# MaTouch_DevKit_Relay_V1_2.net
KiCad netlist of a schematic drawn in EAGLE
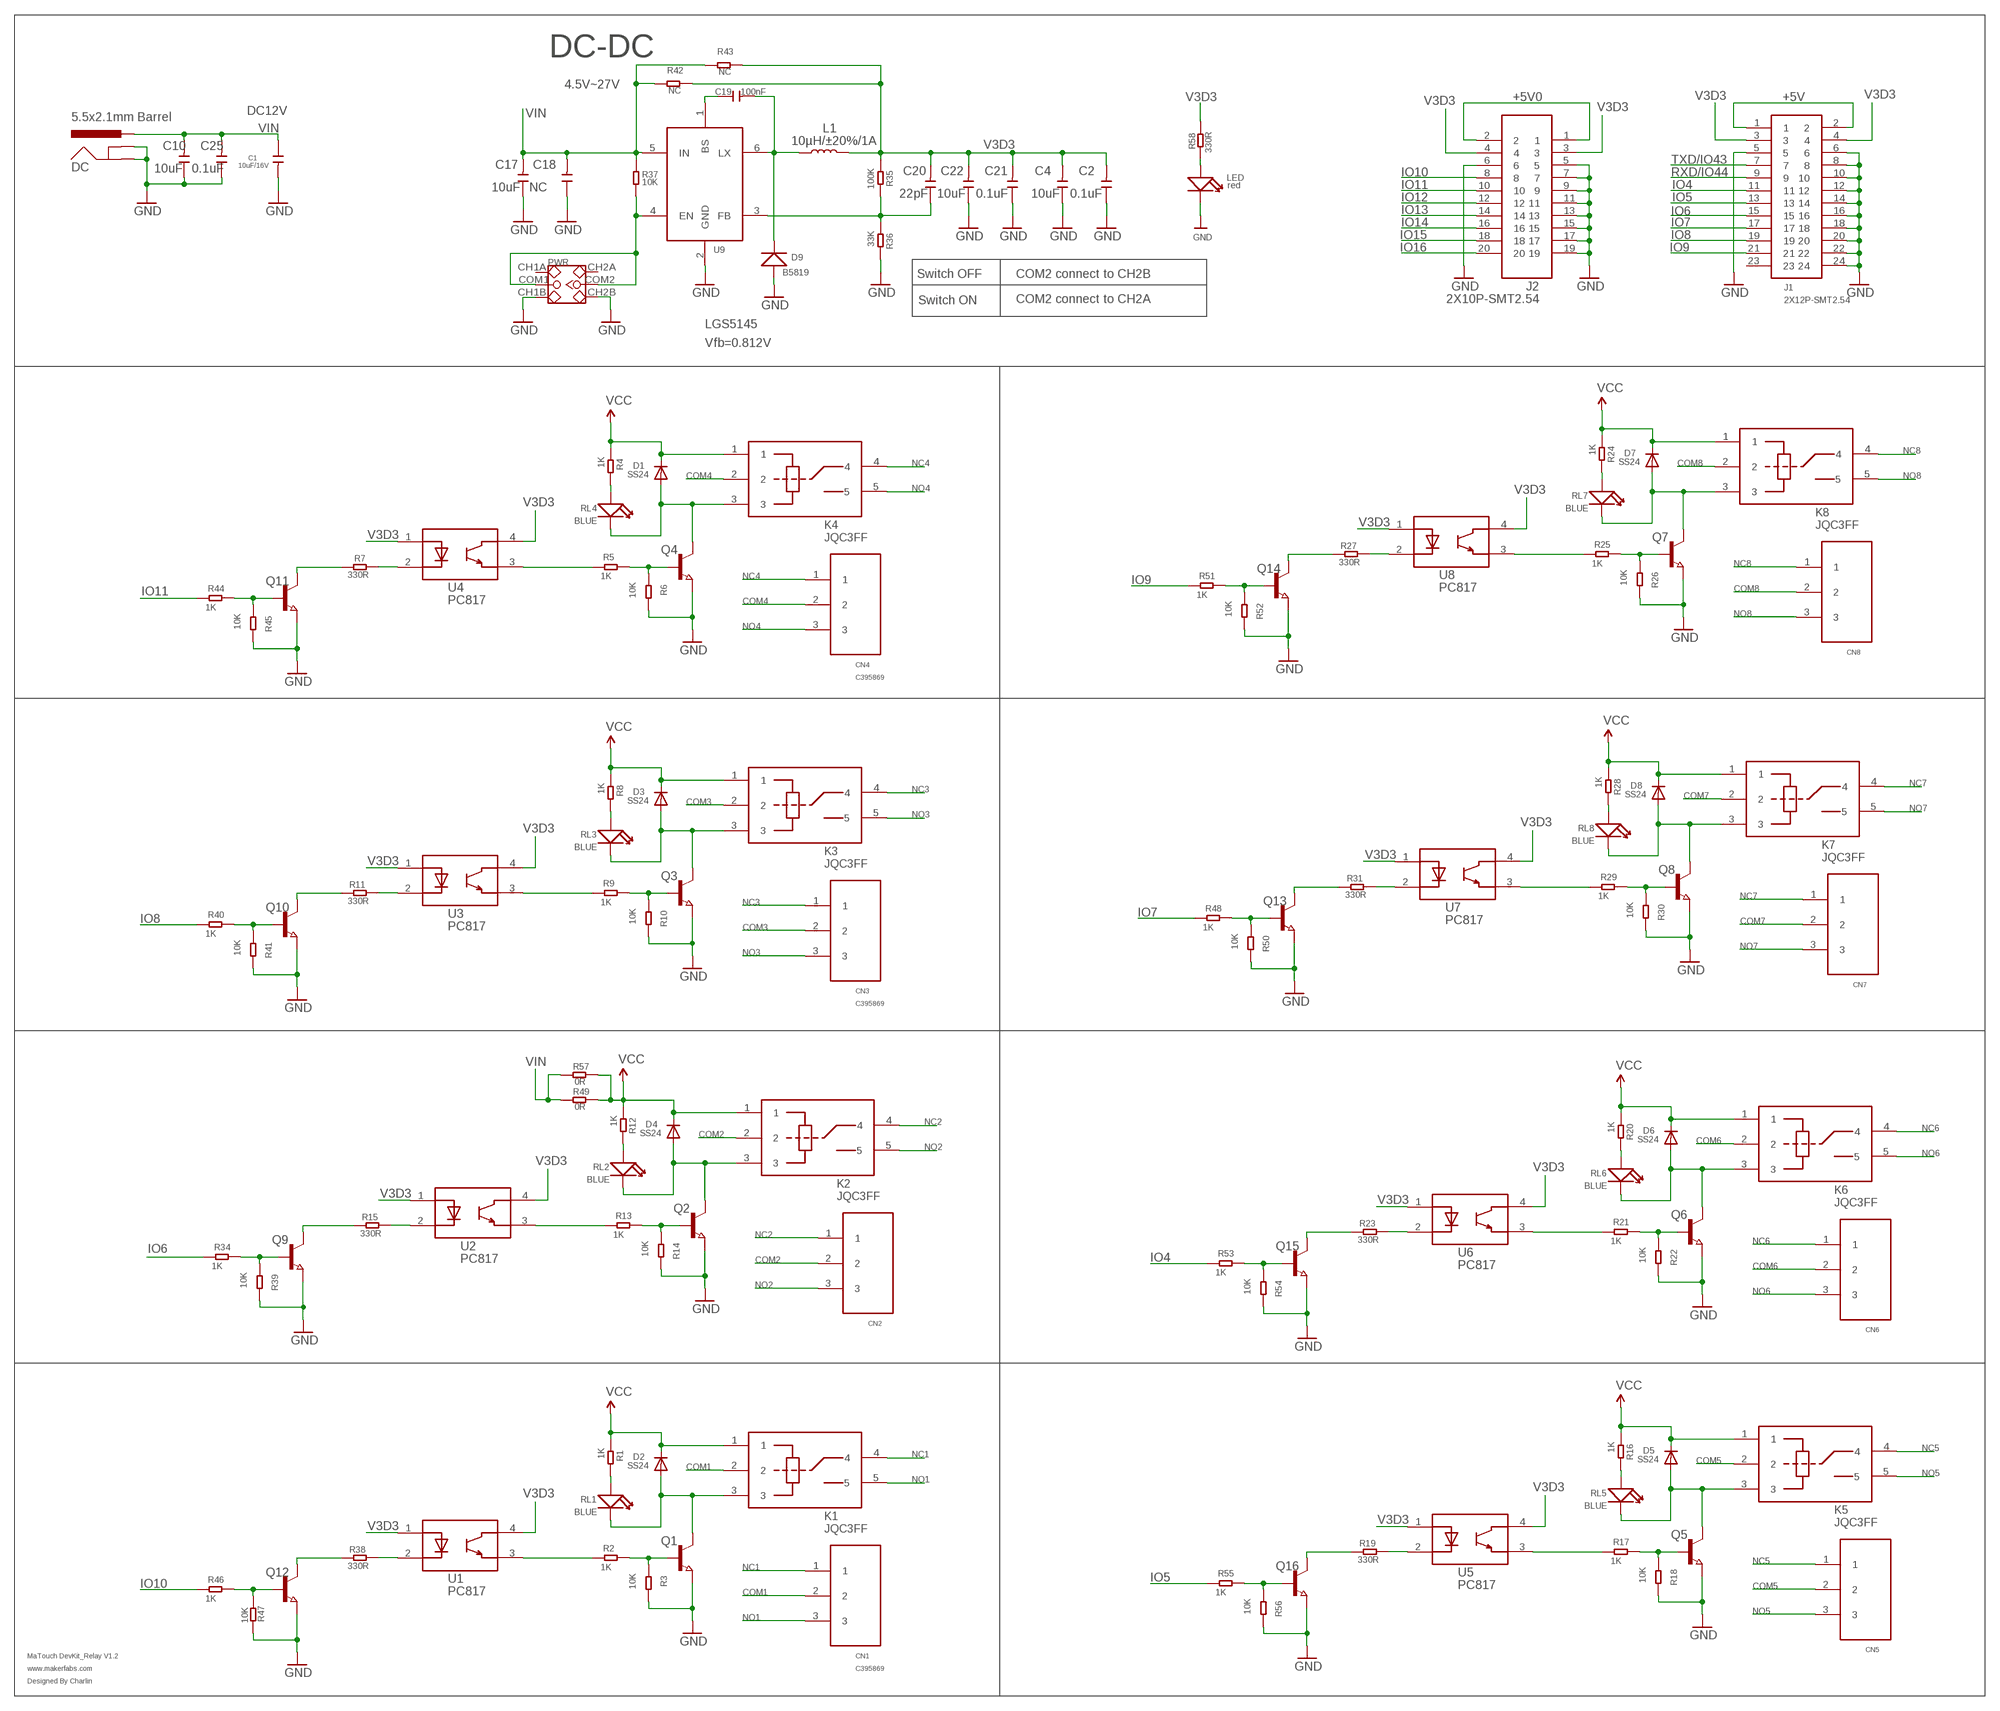
[diagram p0: schematic, sheet 1]

(export (version "E")
  (design (tool "Eeschema 10.0.6"))
  (components
    (comp (ref "C1")
      (value "10uF/16V")
      (footprint "eagle-import:0603")
      (libsource (lib "eagle-import") (part "C-0603"))
    )
    (comp (ref "C2")
      (value "0.1uF")
      (footprint "eagle-import:0603")
      (libsource (lib "eagle-import") (part "C-0603"))
    )
    (comp (ref "C4")
      (value "10uF")
      (footprint "eagle-import:0603")
      (libsource (lib "eagle-import") (part "C-0603"))
    )
    (comp (ref "C10")
      (value "10uF")
      (footprint "eagle-import:0603")
      (libsource (lib "eagle-import") (part "C-0603"))
    )
    (comp (ref "C17")
      (value "10uF")
      (footprint "eagle-import:0603")
      (libsource (lib "eagle-import") (part "C-0603"))
    )
    (comp (ref "C18")
      (value "NC")
      (footprint "eagle-import:0603")
      (libsource (lib "eagle-import") (part "C-0603"))
    )
    (comp (ref "C19")
      (value "100nF")
      (footprint "eagle-import:0603")
      (libsource (lib "eagle-import") (part "C-0603"))
    )
    (comp (ref "C20")
      (value "22pF")
      (footprint "eagle-import:0603")
      (libsource (lib "eagle-import") (part "C-0603"))
    )
    (comp (ref "C21")
      (value "0.1uF")
      (footprint "eagle-import:0603")
      (libsource (lib "eagle-import") (part "C-0603"))
    )
    (comp (ref "C22")
      (value "10uF")
      (footprint "eagle-import:0603")
      (libsource (lib "eagle-import") (part "C-0603"))
    )
    (comp (ref "C25")
      (value "0.1uF")
      (footprint "eagle-import:0603")
      (libsource (lib "eagle-import") (part "C-0603"))
    )
    (comp (ref "CN1")
      (value "C395869")
      (footprint "eagle-import:PIN_3P")
      (libsource (lib "eagle-import") (part "C395869"))
    )
    (comp (ref "CN2")
      (value "C395869")
      (footprint "eagle-import:PIN_3P")
      (libsource (lib "eagle-import") (part "C395869"))
    )
    (comp (ref "CN3")
      (value "C395869")
      (footprint "eagle-import:PIN_3P")
      (libsource (lib "eagle-import") (part "C395869"))
    )
    (comp (ref "CN4")
      (value "C395869")
      (footprint "eagle-import:PIN_3P")
      (libsource (lib "eagle-import") (part "C395869"))
    )
    (comp (ref "CN5")
      (value "C395869")
      (footprint "eagle-import:PIN_3P")
      (libsource (lib "eagle-import") (part "C395869"))
    )
    (comp (ref "CN6")
      (value "C395869")
      (footprint "eagle-import:PIN_3P")
      (libsource (lib "eagle-import") (part "C395869"))
    )
    (comp (ref "CN7")
      (value "C395869")
      (footprint "eagle-import:PIN_3P")
      (libsource (lib "eagle-import") (part "C395869"))
    )
    (comp (ref "CN8")
      (value "C395869")
      (footprint "eagle-import:PIN_3P")
      (libsource (lib "eagle-import") (part "C395869"))
    )
    (comp (ref "D1")
      (value "SS24")
      (footprint "eagle-import:SMADIODE")
      (libsource (lib "eagle-import") (part "DIODESMA"))
    )
    (comp (ref "D2")
      (value "SS24")
      (footprint "eagle-import:SMADIODE")
      (libsource (lib "eagle-import") (part "DIODESMA"))
    )
    (comp (ref "D3")
      (value "SS24")
      (footprint "eagle-import:SMADIODE")
      (libsource (lib "eagle-import") (part "DIODESMA"))
    )
    (comp (ref "D4")
      (value "SS24")
      (footprint "eagle-import:SMADIODE")
      (libsource (lib "eagle-import") (part "DIODESMA"))
    )
    (comp (ref "D5")
      (value "SS24")
      (footprint "eagle-import:SMADIODE")
      (libsource (lib "eagle-import") (part "DIODESMA"))
    )
    (comp (ref "D6")
      (value "SS24")
      (footprint "eagle-import:SMADIODE")
      (libsource (lib "eagle-import") (part "DIODESMA"))
    )
    (comp (ref "D7")
      (value "SS24")
      (footprint "eagle-import:SMADIODE")
      (libsource (lib "eagle-import") (part "DIODESMA"))
    )
    (comp (ref "D8")
      (value "SS24")
      (footprint "eagle-import:SMADIODE")
      (libsource (lib "eagle-import") (part "DIODESMA"))
    )
    (comp (ref "D9")
      (value "B5819")
      (footprint "eagle-import:SOD123")
      (libsource (lib "eagle-import") (part "D'1206'"))
    )
    (comp (ref "DC")
      (value "5.5x2.1mm Barrel")
      (footprint "eagle-import:POWER_JACK_SMD")
      (libsource (lib "eagle-import") (part "POWER_JACKSMD"))
    )
    (comp (ref "J1")
      (value "2X12P-SMT2.54")
      (footprint "eagle-import:2X12P-SMT2.54")
      (libsource (lib "eagle-import") (part "2X12P-SMT2.54"))
    )
    (comp (ref "J2")
      (value "2X10P-SMT2.54")
      (footprint "eagle-import:2X10P-SMT2.54")
      (libsource (lib "eagle-import") (part "2X10P-SMT2.54"))
    )
    (comp (ref "K1")
      (value "JQC3FF")
      (footprint "eagle-import:DIP5_JQC3FF")
      (libsource (lib "eagle-import") (part "JQC3FF"))
    )
    (comp (ref "K2")
      (value "JQC3FF")
      (footprint "eagle-import:DIP5_JQC3FF")
      (libsource (lib "eagle-import") (part "JQC3FF"))
    )
    (comp (ref "K3")
      (value "JQC3FF")
      (footprint "eagle-import:DIP5_JQC3FF")
      (libsource (lib "eagle-import") (part "JQC3FF"))
    )
    (comp (ref "K4")
      (value "JQC3FF")
      (footprint "eagle-import:DIP5_JQC3FF")
      (libsource (lib "eagle-import") (part "JQC3FF"))
    )
    (comp (ref "K5")
      (value "JQC3FF")
      (footprint "eagle-import:DIP5_JQC3FF")
      (libsource (lib "eagle-import") (part "JQC3FF"))
    )
    (comp (ref "K6")
      (value "JQC3FF")
      (footprint "eagle-import:DIP5_JQC3FF")
      (libsource (lib "eagle-import") (part "JQC3FF"))
    )
    (comp (ref "K7")
      (value "JQC3FF")
      (footprint "eagle-import:DIP5_JQC3FF")
      (libsource (lib "eagle-import") (part "JQC3FF"))
    )
    (comp (ref "K8")
      (value "JQC3FF")
      (footprint "eagle-import:DIP5_JQC3FF")
      (libsource (lib "eagle-import") (part "JQC3FF"))
    )
    (comp (ref "L1")
      (value "10µH/±20%/1A")
      (footprint "eagle-import:SRN6045")
      (libsource (lib "eagle-import") (part "INDUCTOR-SRN6045-33UH"))
    )
    (comp (ref "LED")
      (value "red")
      (footprint "eagle-import:DISCRETE_LED-0603")
      (libsource (lib "eagle-import") (part "DISCRETE_LED0603"))
    )
    (comp (ref "PWR")
      (value "SWITCH-2CH-6P")
      (footprint "eagle-import:6P-2CH-2.54-7.6X3.0")
      (libsource (lib "eagle-import") (part "SWITCH-2CH-6P"))
    )
    (comp (ref "Q1")
      (value "NPN-TRANSISTOR_SOT23")
      (footprint "eagle-import:SOT23")
      (libsource (lib "eagle-import") (part "NPN-TRANSISTOR_SOT23"))
    )
    (comp (ref "Q2")
      (value "NPN-TRANSISTOR_SOT23")
      (footprint "eagle-import:SOT23")
      (libsource (lib "eagle-import") (part "NPN-TRANSISTOR_SOT23"))
    )
    (comp (ref "Q3")
      (value "NPN-TRANSISTOR_SOT23")
      (footprint "eagle-import:SOT23")
      (libsource (lib "eagle-import") (part "NPN-TRANSISTOR_SOT23"))
    )
    (comp (ref "Q4")
      (value "NPN-TRANSISTOR_SOT23")
      (footprint "eagle-import:SOT23")
      (libsource (lib "eagle-import") (part "NPN-TRANSISTOR_SOT23"))
    )
    (comp (ref "Q5")
      (value "NPN-TRANSISTOR_SOT23")
      (footprint "eagle-import:SOT23")
      (libsource (lib "eagle-import") (part "NPN-TRANSISTOR_SOT23"))
    )
    (comp (ref "Q6")
      (value "NPN-TRANSISTOR_SOT23")
      (footprint "eagle-import:SOT23")
      (libsource (lib "eagle-import") (part "NPN-TRANSISTOR_SOT23"))
    )
    (comp (ref "Q7")
      (value "NPN-TRANSISTOR_SOT23")
      (footprint "eagle-import:SOT23")
      (libsource (lib "eagle-import") (part "NPN-TRANSISTOR_SOT23"))
    )
    (comp (ref "Q8")
      (value "NPN-TRANSISTOR_SOT23")
      (footprint "eagle-import:SOT23")
      (libsource (lib "eagle-import") (part "NPN-TRANSISTOR_SOT23"))
    )
    (comp (ref "Q9")
      (value "NPN-TRANSISTOR_SOT23")
      (footprint "eagle-import:SOT23")
      (libsource (lib "eagle-import") (part "NPN-TRANSISTOR_SOT23"))
    )
    (comp (ref "Q10")
      (value "NPN-TRANSISTOR_SOT23")
      (footprint "eagle-import:SOT23")
      (libsource (lib "eagle-import") (part "NPN-TRANSISTOR_SOT23"))
    )
    (comp (ref "Q11")
      (value "NPN-TRANSISTOR_SOT23")
      (footprint "eagle-import:SOT23")
      (libsource (lib "eagle-import") (part "NPN-TRANSISTOR_SOT23"))
    )
    (comp (ref "Q12")
      (value "NPN-TRANSISTOR_SOT23")
      (footprint "eagle-import:SOT23")
      (libsource (lib "eagle-import") (part "NPN-TRANSISTOR_SOT23"))
    )
    (comp (ref "Q13")
      (value "NPN-TRANSISTOR_SOT23")
      (footprint "eagle-import:SOT23")
      (libsource (lib "eagle-import") (part "NPN-TRANSISTOR_SOT23"))
    )
    (comp (ref "Q14")
      (value "NPN-TRANSISTOR_SOT23")
      (footprint "eagle-import:SOT23")
      (libsource (lib "eagle-import") (part "NPN-TRANSISTOR_SOT23"))
    )
    (comp (ref "Q15")
      (value "NPN-TRANSISTOR_SOT23")
      (footprint "eagle-import:SOT23")
      (libsource (lib "eagle-import") (part "NPN-TRANSISTOR_SOT23"))
    )
    (comp (ref "Q16")
      (value "NPN-TRANSISTOR_SOT23")
      (footprint "eagle-import:SOT23")
      (libsource (lib "eagle-import") (part "NPN-TRANSISTOR_SOT23"))
    )
    (comp (ref "R1")
      (value "1K")
      (footprint "eagle-import:R0603")
      (libsource (lib "eagle-import") (part "R-0603"))
    )
    (comp (ref "R2")
      (value "1K")
      (footprint "eagle-import:R0603")
      (libsource (lib "eagle-import") (part "R-0603"))
    )
    (comp (ref "R3")
      (value "10K")
      (footprint "eagle-import:R0603")
      (libsource (lib "eagle-import") (part "R-0603"))
    )
    (comp (ref "R4")
      (value "1K")
      (footprint "eagle-import:R0603")
      (libsource (lib "eagle-import") (part "R-0603"))
    )
    (comp (ref "R5")
      (value "1K")
      (footprint "eagle-import:R0603")
      (libsource (lib "eagle-import") (part "R-0603"))
    )
    (comp (ref "R6")
      (value "10K")
      (footprint "eagle-import:R0603")
      (libsource (lib "eagle-import") (part "R-0603"))
    )
    (comp (ref "R7")
      (value "330R")
      (footprint "eagle-import:R0603")
      (libsource (lib "eagle-import") (part "R-0603"))
    )
    (comp (ref "R8")
      (value "1K")
      (footprint "eagle-import:R0603")
      (libsource (lib "eagle-import") (part "R-0603"))
    )
    (comp (ref "R9")
      (value "1K")
      (footprint "eagle-import:R0603")
      (libsource (lib "eagle-import") (part "R-0603"))
    )
    (comp (ref "R10")
      (value "10K")
      (footprint "eagle-import:R0603")
      (libsource (lib "eagle-import") (part "R-0603"))
    )
    (comp (ref "R11")
      (value "330R")
      (footprint "eagle-import:R0603")
      (libsource (lib "eagle-import") (part "R-0603"))
    )
    (comp (ref "R12")
      (value "1K")
      (footprint "eagle-import:R0603")
      (libsource (lib "eagle-import") (part "R-0603"))
    )
    (comp (ref "R13")
      (value "1K")
      (footprint "eagle-import:R0603")
      (libsource (lib "eagle-import") (part "R-0603"))
    )
    (comp (ref "R14")
      (value "10K")
      (footprint "eagle-import:R0603")
      (libsource (lib "eagle-import") (part "R-0603"))
    )
    (comp (ref "R15")
      (value "330R")
      (footprint "eagle-import:R0603")
      (libsource (lib "eagle-import") (part "R-0603"))
    )
    (comp (ref "R16")
      (value "1K")
      (footprint "eagle-import:R0603")
      (libsource (lib "eagle-import") (part "R-0603"))
    )
    (comp (ref "R17")
      (value "1K")
      (footprint "eagle-import:R0603")
      (libsource (lib "eagle-import") (part "R-0603"))
    )
    (comp (ref "R18")
      (value "10K")
      (footprint "eagle-import:R0603")
      (libsource (lib "eagle-import") (part "R-0603"))
    )
    (comp (ref "R19")
      (value "330R")
      (footprint "eagle-import:R0603")
      (libsource (lib "eagle-import") (part "R-0603"))
    )
    (comp (ref "R20")
      (value "1K")
      (footprint "eagle-import:R0603")
      (libsource (lib "eagle-import") (part "R-0603"))
    )
    (comp (ref "R21")
      (value "1K")
      (footprint "eagle-import:R0603")
      (libsource (lib "eagle-import") (part "R-0603"))
    )
    (comp (ref "R22")
      (value "10K")
      (footprint "eagle-import:R0603")
      (libsource (lib "eagle-import") (part "R-0603"))
    )
    (comp (ref "R23")
      (value "330R")
      (footprint "eagle-import:R0603")
      (libsource (lib "eagle-import") (part "R-0603"))
    )
    (comp (ref "R24")
      (value "1K")
      (footprint "eagle-import:R0603")
      (libsource (lib "eagle-import") (part "R-0603"))
    )
    (comp (ref "R25")
      (value "1K")
      (footprint "eagle-import:R0603")
      (libsource (lib "eagle-import") (part "R-0603"))
    )
    (comp (ref "R26")
      (value "10K")
      (footprint "eagle-import:R0603")
      (libsource (lib "eagle-import") (part "R-0603"))
    )
    (comp (ref "R27")
      (value "330R")
      (footprint "eagle-import:R0603")
      (libsource (lib "eagle-import") (part "R-0603"))
    )
    (comp (ref "R28")
      (value "1K")
      (footprint "eagle-import:R0603")
      (libsource (lib "eagle-import") (part "R-0603"))
    )
    (comp (ref "R29")
      (value "1K")
      (footprint "eagle-import:R0603")
      (libsource (lib "eagle-import") (part "R-0603"))
    )
    (comp (ref "R30")
      (value "10K")
      (footprint "eagle-import:R0603")
      (libsource (lib "eagle-import") (part "R-0603"))
    )
    (comp (ref "R31")
      (value "330R")
      (footprint "eagle-import:R0603")
      (libsource (lib "eagle-import") (part "R-0603"))
    )
    (comp (ref "R34")
      (value "1K")
      (footprint "eagle-import:R0603")
      (libsource (lib "eagle-import") (part "R-0603"))
    )
    (comp (ref "R35")
      (value "100K")
      (footprint "eagle-import:R0603")
      (libsource (lib "eagle-import") (part "R-0603"))
    )
    (comp (ref "R36")
      (value "33K")
      (footprint "eagle-import:R0603")
      (libsource (lib "eagle-import") (part "R-0603"))
    )
    (comp (ref "R37")
      (value "10K")
      (footprint "eagle-import:R0603")
      (libsource (lib "eagle-import") (part "R-0603"))
    )
    (comp (ref "R38")
      (value "330R")
      (footprint "eagle-import:R0603")
      (libsource (lib "eagle-import") (part "R-0603"))
    )
    (comp (ref "R39")
      (value "10K")
      (footprint "eagle-import:R0603")
      (libsource (lib "eagle-import") (part "R-0603"))
    )
    (comp (ref "R40")
      (value "1K")
      (footprint "eagle-import:R0603")
      (libsource (lib "eagle-import") (part "R-0603"))
    )
    (comp (ref "R41")
      (value "10K")
      (footprint "eagle-import:R0603")
      (libsource (lib "eagle-import") (part "R-0603"))
    )
    (comp (ref "R42")
      (value "NC")
      (footprint "eagle-import:R0603")
      (libsource (lib "eagle-import") (part "R-0603"))
    )
    (comp (ref "R43")
      (value "NC")
      (footprint "eagle-import:R0603")
      (libsource (lib "eagle-import") (part "R-0603"))
    )
    (comp (ref "R44")
      (value "1K")
      (footprint "eagle-import:R0603")
      (libsource (lib "eagle-import") (part "R-0603"))
    )
    (comp (ref "R45")
      (value "10K")
      (footprint "eagle-import:R0603")
      (libsource (lib "eagle-import") (part "R-0603"))
    )
    (comp (ref "R46")
      (value "1K")
      (footprint "eagle-import:R0603")
      (libsource (lib "eagle-import") (part "R-0603"))
    )
    (comp (ref "R47")
      (value "10K")
      (footprint "eagle-import:R0603")
      (libsource (lib "eagle-import") (part "R-0603"))
    )
    (comp (ref "R48")
      (value "1K")
      (footprint "eagle-import:R0603")
      (libsource (lib "eagle-import") (part "R-0603"))
    )
    (comp (ref "R49")
      (value "0R")
      (footprint "eagle-import:R0603")
      (libsource (lib "eagle-import") (part "R-0603"))
    )
    (comp (ref "R50")
      (value "10K")
      (footprint "eagle-import:R0603")
      (libsource (lib "eagle-import") (part "R-0603"))
    )
    (comp (ref "R51")
      (value "1K")
      (footprint "eagle-import:R0603")
      (libsource (lib "eagle-import") (part "R-0603"))
    )
    (comp (ref "R52")
      (value "10K")
      (footprint "eagle-import:R0603")
      (libsource (lib "eagle-import") (part "R-0603"))
    )
    (comp (ref "R53")
      (value "1K")
      (footprint "eagle-import:R0603")
      (libsource (lib "eagle-import") (part "R-0603"))
    )
    (comp (ref "R54")
      (value "10K")
      (footprint "eagle-import:R0603")
      (libsource (lib "eagle-import") (part "R-0603"))
    )
    (comp (ref "R55")
      (value "1K")
      (footprint "eagle-import:R0603")
      (libsource (lib "eagle-import") (part "R-0603"))
    )
    (comp (ref "R56")
      (value "10K")
      (footprint "eagle-import:R0603")
      (libsource (lib "eagle-import") (part "R-0603"))
    )
    (comp (ref "R57")
      (value "0R")
      (footprint "eagle-import:R0603")
      (libsource (lib "eagle-import") (part "R-0603"))
    )
    (comp (ref "R58")
      (value "330R")
      (footprint "eagle-import:R0603")
      (libsource (lib "eagle-import") (part "R-0603"))
    )
    (comp (ref "RL1")
      (value "BLUE")
      (footprint "eagle-import:LED-0603")
      (libsource (lib "eagle-import") (part "LED'0603'"))
    )
    (comp (ref "RL2")
      (value "BLUE")
      (footprint "eagle-import:LED-0603")
      (libsource (lib "eagle-import") (part "LED'0603'"))
    )
    (comp (ref "RL3")
      (value "BLUE")
      (footprint "eagle-import:LED-0603")
      (libsource (lib "eagle-import") (part "LED'0603'"))
    )
    (comp (ref "RL4")
      (value "BLUE")
      (footprint "eagle-import:LED-0603")
      (libsource (lib "eagle-import") (part "LED'0603'"))
    )
    (comp (ref "RL5")
      (value "BLUE")
      (footprint "eagle-import:LED-0603")
      (libsource (lib "eagle-import") (part "LED'0603'"))
    )
    (comp (ref "RL6")
      (value "BLUE")
      (footprint "eagle-import:LED-0603")
      (libsource (lib "eagle-import") (part "LED'0603'"))
    )
    (comp (ref "RL7")
      (value "BLUE")
      (footprint "eagle-import:LED-0603")
      (libsource (lib "eagle-import") (part "LED'0603'"))
    )
    (comp (ref "RL8")
      (value "BLUE")
      (footprint "eagle-import:LED-0603")
      (libsource (lib "eagle-import") (part "LED'0603'"))
    )
    (comp (ref "U1")
      (value "PC817")
      (footprint "eagle-import:SMD4-254P-1016L460W")
      (libsource (lib "eagle-import") (part "PC817"))
    )
    (comp (ref "U2")
      (value "PC817")
      (footprint "eagle-import:SMD4-254P-1016L460W")
      (libsource (lib "eagle-import") (part "PC817"))
    )
    (comp (ref "U3")
      (value "PC817")
      (footprint "eagle-import:SMD4-254P-1016L460W")
      (libsource (lib "eagle-import") (part "PC817"))
    )
    (comp (ref "U4")
      (value "PC817")
      (footprint "eagle-import:SMD4-254P-1016L460W")
      (libsource (lib "eagle-import") (part "PC817"))
    )
    (comp (ref "U5")
      (value "PC817")
      (footprint "eagle-import:SMD4-254P-1016L460W")
      (libsource (lib "eagle-import") (part "PC817"))
    )
    (comp (ref "U6")
      (value "PC817")
      (footprint "eagle-import:SMD4-254P-1016L460W")
      (libsource (lib "eagle-import") (part "PC817"))
    )
    (comp (ref "U7")
      (value "PC817")
      (footprint "eagle-import:SMD4-254P-1016L460W")
      (libsource (lib "eagle-import") (part "PC817"))
    )
    (comp (ref "U8")
      (value "PC817")
      (footprint "eagle-import:SMD4-254P-1016L460W")
      (libsource (lib "eagle-import") (part "PC817"))
    )
    (comp (ref "U9")
      (value "SY8201ABC")
      (footprint "eagle-import:SOT-23-6")
      (libsource (lib "eagle-import") (part "SY8201ABC"))
    )
  )
  (nets
    (net (code "1") (name "/+5V") (class "Default")
      (node (ref "J1") (pin "1") (pinfunction "1_1") (pintype "bidirectional"))
      (node (ref "J1") (pin "2") (pinfunction "2_2") (pintype "bidirectional"))
    )
    (net (code "2") (name "/+5V0") (class "Default")
      (node (ref "J2") (pin "1") (pinfunction "1_1") (pintype "bidirectional"))
      (node (ref "J2") (pin "2") (pinfunction "2_2") (pintype "bidirectional"))
    )
    (net (code "3") (name "/COM1") (class "Default")
      (node (ref "CN1") (pin "2") (pinfunction "2_2") (pintype "bidirectional"))
      (node (ref "K1") (pin "2") (pinfunction "2_2") (pintype "bidirectional"))
    )
    (net (code "4") (name "/COM2") (class "Default")
      (node (ref "CN2") (pin "2") (pinfunction "2_2") (pintype "bidirectional"))
      (node (ref "K2") (pin "2") (pinfunction "2_2") (pintype "bidirectional"))
    )
    (net (code "5") (name "/COM3") (class "Default")
      (node (ref "CN3") (pin "2") (pinfunction "2_2") (pintype "bidirectional"))
      (node (ref "K3") (pin "2") (pinfunction "2_2") (pintype "bidirectional"))
    )
    (net (code "6") (name "/COM4") (class "Default")
      (node (ref "CN4") (pin "2") (pinfunction "2_2") (pintype "bidirectional"))
      (node (ref "K4") (pin "2") (pinfunction "2_2") (pintype "bidirectional"))
    )
    (net (code "7") (name "/COM5") (class "Default")
      (node (ref "CN5") (pin "2") (pinfunction "2_2") (pintype "bidirectional"))
      (node (ref "K5") (pin "2") (pinfunction "2_2") (pintype "bidirectional"))
    )
    (net (code "8") (name "/COM6") (class "Default")
      (node (ref "CN6") (pin "2") (pinfunction "2_2") (pintype "bidirectional"))
      (node (ref "K6") (pin "2") (pinfunction "2_2") (pintype "bidirectional"))
    )
    (net (code "9") (name "/COM7") (class "Default")
      (node (ref "CN7") (pin "2") (pinfunction "2_2") (pintype "bidirectional"))
      (node (ref "K7") (pin "2") (pinfunction "2_2") (pintype "bidirectional"))
    )
    (net (code "10") (name "/COM8") (class "Default")
      (node (ref "CN8") (pin "2") (pinfunction "2_2") (pintype "bidirectional"))
      (node (ref "K8") (pin "2") (pinfunction "2_2") (pintype "bidirectional"))
    )
    (net (code "11") (name "/IO4") (class "Default")
      (node (ref "J1") (pin "11") (pinfunction "11_11") (pintype "bidirectional"))
      (node (ref "R53") (pin "1") (pinfunction "1_1") (pintype "passive"))
    )
    (net (code "12") (name "/IO5") (class "Default")
      (node (ref "J1") (pin "13") (pinfunction "13_13") (pintype "bidirectional"))
      (node (ref "R55") (pin "1") (pinfunction "1_1") (pintype "passive"))
    )
    (net (code "13") (name "/IO6") (class "Default")
      (node (ref "J1") (pin "15") (pinfunction "15_15") (pintype "bidirectional"))
      (node (ref "R34") (pin "1") (pinfunction "1_1") (pintype "passive"))
    )
    (net (code "14") (name "/IO7") (class "Default")
      (node (ref "J1") (pin "17") (pinfunction "17_17") (pintype "bidirectional"))
      (node (ref "R48") (pin "1") (pinfunction "1_1") (pintype "passive"))
    )
    (net (code "15") (name "/IO8") (class "Default")
      (node (ref "J1") (pin "19") (pinfunction "19_19") (pintype "bidirectional"))
      (node (ref "R40") (pin "1") (pinfunction "1_1") (pintype "passive"))
    )
    (net (code "16") (name "/IO9") (class "Default")
      (node (ref "J1") (pin "21") (pinfunction "21_21") (pintype "bidirectional"))
      (node (ref "R51") (pin "1") (pinfunction "1_1") (pintype "passive"))
    )
    (net (code "17") (name "/IO10") (class "Default")
      (node (ref "J2") (pin "8") (pinfunction "8_8") (pintype "bidirectional"))
      (node (ref "R46") (pin "1") (pinfunction "1_1") (pintype "passive"))
    )
    (net (code "18") (name "/IO11") (class "Default")
      (node (ref "J2") (pin "10") (pinfunction "10_10") (pintype "bidirectional"))
      (node (ref "R44") (pin "1") (pinfunction "1_1") (pintype "passive"))
    )
    (net (code "19") (name "/IO12") (class "Default")
      (node (ref "J2") (pin "12") (pinfunction "12_12") (pintype "bidirectional"))
    )
    (net (code "20") (name "/IO13") (class "Default")
      (node (ref "J2") (pin "14") (pinfunction "14_14") (pintype "bidirectional"))
    )
    (net (code "21") (name "/IO14") (class "Default")
      (node (ref "J2") (pin "16") (pinfunction "16_16") (pintype "bidirectional"))
    )
    (net (code "22") (name "/IO15") (class "Default")
      (node (ref "J2") (pin "18") (pinfunction "18_18") (pintype "bidirectional"))
    )
    (net (code "23") (name "/IO16") (class "Default")
      (node (ref "J2") (pin "20") (pinfunction "20_20") (pintype "bidirectional"))
    )
    (net (code "24") (name "/NC1") (class "Default")
      (node (ref "CN1") (pin "1") (pinfunction "1_1") (pintype "bidirectional"))
      (node (ref "K1") (pin "4") (pinfunction "4_4") (pintype "bidirectional"))
    )
    (net (code "25") (name "/NC2") (class "Default")
      (node (ref "CN2") (pin "1") (pinfunction "1_1") (pintype "bidirectional"))
      (node (ref "K2") (pin "4") (pinfunction "4_4") (pintype "bidirectional"))
    )
    (net (code "26") (name "/NC3") (class "Default")
      (node (ref "CN3") (pin "1") (pinfunction "1_1") (pintype "bidirectional"))
      (node (ref "K3") (pin "4") (pinfunction "4_4") (pintype "bidirectional"))
    )
    (net (code "27") (name "/NC4") (class "Default")
      (node (ref "CN4") (pin "1") (pinfunction "1_1") (pintype "bidirectional"))
      (node (ref "K4") (pin "4") (pinfunction "4_4") (pintype "bidirectional"))
    )
    (net (code "28") (name "/NC5") (class "Default")
      (node (ref "CN5") (pin "1") (pinfunction "1_1") (pintype "bidirectional"))
      (node (ref "K5") (pin "4") (pinfunction "4_4") (pintype "bidirectional"))
    )
    (net (code "29") (name "/NC6") (class "Default")
      (node (ref "CN6") (pin "1") (pinfunction "1_1") (pintype "bidirectional"))
      (node (ref "K6") (pin "4") (pinfunction "4_4") (pintype "bidirectional"))
    )
    (net (code "30") (name "/NC7") (class "Default")
      (node (ref "CN7") (pin "1") (pinfunction "1_1") (pintype "bidirectional"))
      (node (ref "K7") (pin "4") (pinfunction "4_4") (pintype "bidirectional"))
    )
    (net (code "31") (name "/NC8") (class "Default")
      (node (ref "CN8") (pin "1") (pinfunction "1_1") (pintype "bidirectional"))
      (node (ref "K8") (pin "4") (pinfunction "4_4") (pintype "bidirectional"))
    )
    (net (code "32") (name "/NO1") (class "Default")
      (node (ref "CN1") (pin "3") (pinfunction "3_3") (pintype "bidirectional"))
      (node (ref "K1") (pin "5") (pinfunction "5_5") (pintype "bidirectional"))
    )
    (net (code "33") (name "/NO2") (class "Default")
      (node (ref "CN2") (pin "3") (pinfunction "3_3") (pintype "bidirectional"))
      (node (ref "K2") (pin "5") (pinfunction "5_5") (pintype "bidirectional"))
    )
    (net (code "34") (name "/NO3") (class "Default")
      (node (ref "CN3") (pin "3") (pinfunction "3_3") (pintype "bidirectional"))
      (node (ref "K3") (pin "5") (pinfunction "5_5") (pintype "bidirectional"))
    )
    (net (code "35") (name "/NO4") (class "Default")
      (node (ref "CN4") (pin "3") (pinfunction "3_3") (pintype "bidirectional"))
      (node (ref "K4") (pin "5") (pinfunction "5_5") (pintype "bidirectional"))
    )
    (net (code "36") (name "/NO5") (class "Default")
      (node (ref "CN5") (pin "3") (pinfunction "3_3") (pintype "bidirectional"))
      (node (ref "K5") (pin "5") (pinfunction "5_5") (pintype "bidirectional"))
    )
    (net (code "37") (name "/NO6") (class "Default")
      (node (ref "CN6") (pin "3") (pinfunction "3_3") (pintype "bidirectional"))
      (node (ref "K6") (pin "5") (pinfunction "5_5") (pintype "bidirectional"))
    )
    (net (code "38") (name "/NO7") (class "Default")
      (node (ref "CN7") (pin "3") (pinfunction "3_3") (pintype "bidirectional"))
      (node (ref "K7") (pin "5") (pinfunction "5_5") (pintype "bidirectional"))
    )
    (net (code "39") (name "/NO8") (class "Default")
      (node (ref "CN8") (pin "3") (pinfunction "3_3") (pintype "bidirectional"))
      (node (ref "K8") (pin "5") (pinfunction "5_5") (pintype "bidirectional"))
    )
    (net (code "40") (name "/RXD{slash}IO44") (class "Default")
      (node (ref "J1") (pin "9") (pinfunction "9_9") (pintype "bidirectional"))
    )
    (net (code "41") (name "/TXD{slash}IO43") (class "Default")
      (node (ref "J1") (pin "7") (pinfunction "7_7") (pintype "bidirectional"))
    )
    (net (code "42") (name "/V3D3") (class "Default")
      (node (ref "C2") (pin "2") (pinfunction "2_2") (pintype "passive"))
      (node (ref "C20") (pin "2") (pinfunction "2_2") (pintype "passive"))
      (node (ref "C21") (pin "2") (pinfunction "2_2") (pintype "passive"))
      (node (ref "C22") (pin "2") (pinfunction "2_2") (pintype "passive"))
      (node (ref "C4") (pin "2") (pinfunction "2_2") (pintype "passive"))
      (node (ref "J1") (pin "3") (pinfunction "3_3") (pintype "bidirectional"))
      (node (ref "J1") (pin "4") (pinfunction "4_4") (pintype "bidirectional"))
      (node (ref "J2") (pin "3") (pinfunction "3_3") (pintype "bidirectional"))
      (node (ref "J2") (pin "4") (pinfunction "4_4") (pintype "bidirectional"))
      (node (ref "L1") (pin "2") (pinfunction "2_2") (pintype "passive"))
      (node (ref "R35") (pin "1") (pinfunction "1_1") (pintype "passive"))
      (node (ref "R42") (pin "2") (pinfunction "2_2") (pintype "passive"))
      (node (ref "R43") (pin "2") (pinfunction "2_2") (pintype "passive"))
      (node (ref "R58") (pin "2") (pinfunction "2_2") (pintype "passive"))
      (node (ref "U1") (pin "1") (pinfunction "1_1") (pintype "bidirectional"))
      (node (ref "U1") (pin "4") (pinfunction "4_4") (pintype "bidirectional"))
      (node (ref "U2") (pin "1") (pinfunction "1_1") (pintype "bidirectional"))
      (node (ref "U2") (pin "4") (pinfunction "4_4") (pintype "bidirectional"))
      (node (ref "U3") (pin "1") (pinfunction "1_1") (pintype "bidirectional"))
      (node (ref "U3") (pin "4") (pinfunction "4_4") (pintype "bidirectional"))
      (node (ref "U4") (pin "1") (pinfunction "1_1") (pintype "bidirectional"))
      (node (ref "U4") (pin "4") (pinfunction "4_4") (pintype "bidirectional"))
      (node (ref "U5") (pin "1") (pinfunction "1_1") (pintype "bidirectional"))
      (node (ref "U5") (pin "4") (pinfunction "4_4") (pintype "bidirectional"))
      (node (ref "U6") (pin "1") (pinfunction "1_1") (pintype "bidirectional"))
      (node (ref "U6") (pin "4") (pinfunction "4_4") (pintype "bidirectional"))
      (node (ref "U7") (pin "1") (pinfunction "1_1") (pintype "bidirectional"))
      (node (ref "U7") (pin "4") (pinfunction "4_4") (pintype "bidirectional"))
      (node (ref "U8") (pin "1") (pinfunction "1_1") (pintype "bidirectional"))
      (node (ref "U8") (pin "4") (pinfunction "4_4") (pintype "bidirectional"))
    )
    (net (code "43") (name "/VIN") (class "Default")
      (node (ref "C1") (pin "1") (pinfunction "1_1") (pintype "passive"))
      (node (ref "C10") (pin "2") (pinfunction "2_2") (pintype "passive"))
      (node (ref "C17") (pin "2") (pinfunction "2_2") (pintype "passive"))
      (node (ref "C18") (pin "2") (pinfunction "2_2") (pintype "passive"))
      (node (ref "C25") (pin "2") (pinfunction "2_2") (pintype "passive"))
      (node (ref "DC") (pin "VIN0") (pinfunction "PWR_VIN0") (pintype "bidirectional"))
      (node (ref "R37") (pin "1") (pinfunction "1_1") (pintype "passive"))
      (node (ref "R42") (pin "1") (pinfunction "1_1") (pintype "passive"))
      (node (ref "R43") (pin "1") (pinfunction "1_1") (pintype "passive"))
      (node (ref "R49") (pin "1") (pinfunction "1_1") (pintype "passive"))
      (node (ref "R57") (pin "1") (pinfunction "1_1") (pintype "passive"))
      (node (ref "U9") (pin "5") (pinfunction "IN_5") (pintype "bidirectional"))
    )
    (net (code "44") (name "GND") (class "Default")
      (node (ref "C1") (pin "2") (pinfunction "2_2") (pintype "passive"))
      (node (ref "C10") (pin "1") (pinfunction "1_1") (pintype "passive"))
      (node (ref "C17") (pin "1") (pinfunction "1_1") (pintype "passive"))
      (node (ref "C18") (pin "1") (pinfunction "1_1") (pintype "passive"))
      (node (ref "C2") (pin "1") (pinfunction "1_1") (pintype "passive"))
      (node (ref "C21") (pin "1") (pinfunction "1_1") (pintype "passive"))
      (node (ref "C22") (pin "1") (pinfunction "1_1") (pintype "passive"))
      (node (ref "C25") (pin "1") (pinfunction "1_1") (pintype "passive"))
      (node (ref "C4") (pin "1") (pinfunction "1_1") (pintype "passive"))
      (node (ref "D9") (pin "+") (pinfunction "+_+") (pintype "passive"))
      (node (ref "DC") (pin "GND") (pinfunction "GNDBREAK_GND") (pintype "bidirectional"))
      (node (ref "DC") (pin "P$4") (pinfunction "GND_P$4") (pintype "bidirectional"))
      (node (ref "J1") (pin "10") (pinfunction "10_10") (pintype "bidirectional"))
      (node (ref "J1") (pin "12") (pinfunction "12_12") (pintype "bidirectional"))
      (node (ref "J1") (pin "14") (pinfunction "14_14") (pintype "bidirectional"))
      (node (ref "J1") (pin "16") (pinfunction "16_16") (pintype "bidirectional"))
      (node (ref "J1") (pin "18") (pinfunction "18_18") (pintype "bidirectional"))
      (node (ref "J1") (pin "20") (pinfunction "20_20") (pintype "bidirectional"))
      (node (ref "J1") (pin "22") (pinfunction "22_22") (pintype "bidirectional"))
      (node (ref "J1") (pin "24") (pinfunction "24_24") (pintype "bidirectional"))
      (node (ref "J1") (pin "5") (pinfunction "5_5") (pintype "bidirectional"))
      (node (ref "J1") (pin "6") (pinfunction "6_6") (pintype "bidirectional"))
      (node (ref "J1") (pin "8") (pinfunction "8_8") (pintype "bidirectional"))
      (node (ref "J2") (pin "11") (pinfunction "11_11") (pintype "bidirectional"))
      (node (ref "J2") (pin "13") (pinfunction "13_13") (pintype "bidirectional"))
      (node (ref "J2") (pin "15") (pinfunction "15_15") (pintype "bidirectional"))
      (node (ref "J2") (pin "17") (pinfunction "17_17") (pintype "bidirectional"))
      (node (ref "J2") (pin "19") (pinfunction "19_19") (pintype "bidirectional"))
      (node (ref "J2") (pin "5") (pinfunction "5_5") (pintype "bidirectional"))
      (node (ref "J2") (pin "6") (pinfunction "6_6") (pintype "bidirectional"))
      (node (ref "J2") (pin "7") (pinfunction "7_7") (pintype "bidirectional"))
      (node (ref "J2") (pin "9") (pinfunction "9_9") (pintype "bidirectional"))
      (node (ref "LED") (pin "-") (pinfunction "-_-") (pintype "passive"))
      (node (ref "PWR") (pin "CH1B") (pinfunction "CH1B_CH1B") (pintype "bidirectional"))
      (node (ref "PWR") (pin "CH2B") (pinfunction "CH2B_CH2B") (pintype "bidirectional"))
      (node (ref "Q1") (pin "2") (pinfunction "E_2") (pintype "passive"))
      (node (ref "Q10") (pin "2") (pinfunction "E_2") (pintype "passive"))
      (node (ref "Q11") (pin "2") (pinfunction "E_2") (pintype "passive"))
      (node (ref "Q12") (pin "2") (pinfunction "E_2") (pintype "passive"))
      (node (ref "Q13") (pin "2") (pinfunction "E_2") (pintype "passive"))
      (node (ref "Q14") (pin "2") (pinfunction "E_2") (pintype "passive"))
      (node (ref "Q15") (pin "2") (pinfunction "E_2") (pintype "passive"))
      (node (ref "Q16") (pin "2") (pinfunction "E_2") (pintype "passive"))
      (node (ref "Q2") (pin "2") (pinfunction "E_2") (pintype "passive"))
      (node (ref "Q3") (pin "2") (pinfunction "E_2") (pintype "passive"))
      (node (ref "Q4") (pin "2") (pinfunction "E_2") (pintype "passive"))
      (node (ref "Q5") (pin "2") (pinfunction "E_2") (pintype "passive"))
      (node (ref "Q6") (pin "2") (pinfunction "E_2") (pintype "passive"))
      (node (ref "Q7") (pin "2") (pinfunction "E_2") (pintype "passive"))
      (node (ref "Q8") (pin "2") (pinfunction "E_2") (pintype "passive"))
      (node (ref "Q9") (pin "2") (pinfunction "E_2") (pintype "passive"))
      (node (ref "R10") (pin "2") (pinfunction "2_2") (pintype "passive"))
      (node (ref "R14") (pin "2") (pinfunction "2_2") (pintype "passive"))
      (node (ref "R18") (pin "2") (pinfunction "2_2") (pintype "passive"))
      (node (ref "R22") (pin "2") (pinfunction "2_2") (pintype "passive"))
      (node (ref "R26") (pin "2") (pinfunction "2_2") (pintype "passive"))
      (node (ref "R3") (pin "2") (pinfunction "2_2") (pintype "passive"))
      (node (ref "R30") (pin "2") (pinfunction "2_2") (pintype "passive"))
      (node (ref "R36") (pin "2") (pinfunction "2_2") (pintype "passive"))
      (node (ref "R39") (pin "2") (pinfunction "2_2") (pintype "passive"))
      (node (ref "R41") (pin "2") (pinfunction "2_2") (pintype "passive"))
      (node (ref "R45") (pin "2") (pinfunction "2_2") (pintype "passive"))
      (node (ref "R47") (pin "2") (pinfunction "2_2") (pintype "passive"))
      (node (ref "R50") (pin "2") (pinfunction "2_2") (pintype "passive"))
      (node (ref "R52") (pin "2") (pinfunction "2_2") (pintype "passive"))
      (node (ref "R54") (pin "2") (pinfunction "2_2") (pintype "passive"))
      (node (ref "R56") (pin "2") (pinfunction "2_2") (pintype "passive"))
      (node (ref "R6") (pin "2") (pinfunction "2_2") (pintype "passive"))
      (node (ref "U9") (pin "2") (pinfunction "GND_2") (pintype "bidirectional"))
    )
    (net (code "45") (name "Net-(LED-Pad+)") (class "Default")
      (node (ref "LED") (pin "+") (pinfunction "+_+") (pintype "passive"))
      (node (ref "R58") (pin "1") (pinfunction "1_1") (pintype "passive"))
    )
    (net (code "46") (name "Net-(Q1-B)") (class "Default")
      (node (ref "Q1") (pin "1") (pinfunction "B_1") (pintype "passive"))
      (node (ref "R2") (pin "2") (pinfunction "2_2") (pintype "passive"))
      (node (ref "R3") (pin "1") (pinfunction "1_1") (pintype "passive"))
    )
    (net (code "47") (name "Net-(Q1-C)") (class "Default")
      (node (ref "D2") (pin "A") (pinfunction "A_A") (pintype "passive"))
      (node (ref "K1") (pin "3") (pinfunction "3_3") (pintype "bidirectional"))
      (node (ref "Q1") (pin "3") (pinfunction "C_3") (pintype "passive"))
      (node (ref "RL1") (pin "-") (pinfunction "-_-") (pintype "passive"))
    )
    (net (code "48") (name "Net-(Q2-B)") (class "Default")
      (node (ref "Q2") (pin "1") (pinfunction "B_1") (pintype "passive"))
      (node (ref "R13") (pin "2") (pinfunction "2_2") (pintype "passive"))
      (node (ref "R14") (pin "1") (pinfunction "1_1") (pintype "passive"))
    )
    (net (code "49") (name "Net-(Q2-C)") (class "Default")
      (node (ref "D4") (pin "A") (pinfunction "A_A") (pintype "passive"))
      (node (ref "K2") (pin "3") (pinfunction "3_3") (pintype "bidirectional"))
      (node (ref "Q2") (pin "3") (pinfunction "C_3") (pintype "passive"))
      (node (ref "RL2") (pin "-") (pinfunction "-_-") (pintype "passive"))
    )
    (net (code "50") (name "Net-(Q3-B)") (class "Default")
      (node (ref "Q3") (pin "1") (pinfunction "B_1") (pintype "passive"))
      (node (ref "R10") (pin "1") (pinfunction "1_1") (pintype "passive"))
      (node (ref "R9") (pin "2") (pinfunction "2_2") (pintype "passive"))
    )
    (net (code "51") (name "Net-(Q3-C)") (class "Default")
      (node (ref "D3") (pin "A") (pinfunction "A_A") (pintype "passive"))
      (node (ref "K3") (pin "3") (pinfunction "3_3") (pintype "bidirectional"))
      (node (ref "Q3") (pin "3") (pinfunction "C_3") (pintype "passive"))
      (node (ref "RL3") (pin "-") (pinfunction "-_-") (pintype "passive"))
    )
    (net (code "52") (name "Net-(Q4-B)") (class "Default")
      (node (ref "Q4") (pin "1") (pinfunction "B_1") (pintype "passive"))
      (node (ref "R5") (pin "2") (pinfunction "2_2") (pintype "passive"))
      (node (ref "R6") (pin "1") (pinfunction "1_1") (pintype "passive"))
    )
    (net (code "53") (name "Net-(Q4-C)") (class "Default")
      (node (ref "D1") (pin "A") (pinfunction "A_A") (pintype "passive"))
      (node (ref "K4") (pin "3") (pinfunction "3_3") (pintype "bidirectional"))
      (node (ref "Q4") (pin "3") (pinfunction "C_3") (pintype "passive"))
      (node (ref "RL4") (pin "-") (pinfunction "-_-") (pintype "passive"))
    )
    (net (code "54") (name "Net-(Q5-B)") (class "Default")
      (node (ref "Q5") (pin "1") (pinfunction "B_1") (pintype "passive"))
      (node (ref "R17") (pin "2") (pinfunction "2_2") (pintype "passive"))
      (node (ref "R18") (pin "1") (pinfunction "1_1") (pintype "passive"))
    )
    (net (code "55") (name "Net-(Q5-C)") (class "Default")
      (node (ref "D5") (pin "A") (pinfunction "A_A") (pintype "passive"))
      (node (ref "K5") (pin "3") (pinfunction "3_3") (pintype "bidirectional"))
      (node (ref "Q5") (pin "3") (pinfunction "C_3") (pintype "passive"))
      (node (ref "RL5") (pin "-") (pinfunction "-_-") (pintype "passive"))
    )
    (net (code "56") (name "Net-(Q6-B)") (class "Default")
      (node (ref "Q6") (pin "1") (pinfunction "B_1") (pintype "passive"))
      (node (ref "R21") (pin "2") (pinfunction "2_2") (pintype "passive"))
      (node (ref "R22") (pin "1") (pinfunction "1_1") (pintype "passive"))
    )
    (net (code "57") (name "Net-(Q6-C)") (class "Default")
      (node (ref "D6") (pin "A") (pinfunction "A_A") (pintype "passive"))
      (node (ref "K6") (pin "3") (pinfunction "3_3") (pintype "bidirectional"))
      (node (ref "Q6") (pin "3") (pinfunction "C_3") (pintype "passive"))
      (node (ref "RL6") (pin "-") (pinfunction "-_-") (pintype "passive"))
    )
    (net (code "58") (name "Net-(Q7-B)") (class "Default")
      (node (ref "Q7") (pin "1") (pinfunction "B_1") (pintype "passive"))
      (node (ref "R25") (pin "2") (pinfunction "2_2") (pintype "passive"))
      (node (ref "R26") (pin "1") (pinfunction "1_1") (pintype "passive"))
    )
    (net (code "59") (name "Net-(Q7-C)") (class "Default")
      (node (ref "D7") (pin "A") (pinfunction "A_A") (pintype "passive"))
      (node (ref "K8") (pin "3") (pinfunction "3_3") (pintype "bidirectional"))
      (node (ref "Q7") (pin "3") (pinfunction "C_3") (pintype "passive"))
      (node (ref "RL7") (pin "-") (pinfunction "-_-") (pintype "passive"))
    )
    (net (code "60") (name "Net-(Q8-B)") (class "Default")
      (node (ref "Q8") (pin "1") (pinfunction "B_1") (pintype "passive"))
      (node (ref "R29") (pin "2") (pinfunction "2_2") (pintype "passive"))
      (node (ref "R30") (pin "1") (pinfunction "1_1") (pintype "passive"))
    )
    (net (code "61") (name "Net-(Q8-C)") (class "Default")
      (node (ref "D8") (pin "A") (pinfunction "A_A") (pintype "passive"))
      (node (ref "K7") (pin "3") (pinfunction "3_3") (pintype "bidirectional"))
      (node (ref "Q8") (pin "3") (pinfunction "C_3") (pintype "passive"))
      (node (ref "RL8") (pin "-") (pinfunction "-_-") (pintype "passive"))
    )
    (net (code "62") (name "Net-(Q9-B)") (class "Default")
      (node (ref "Q9") (pin "1") (pinfunction "B_1") (pintype "passive"))
      (node (ref "R34") (pin "2") (pinfunction "2_2") (pintype "passive"))
      (node (ref "R39") (pin "1") (pinfunction "1_1") (pintype "passive"))
    )
    (net (code "63") (name "Net-(Q9-C)") (class "Default")
      (node (ref "Q9") (pin "3") (pinfunction "C_3") (pintype "passive"))
      (node (ref "R15") (pin "1") (pinfunction "1_1") (pintype "passive"))
    )
    (net (code "64") (name "Net-(Q10-B)") (class "Default")
      (node (ref "Q10") (pin "1") (pinfunction "B_1") (pintype "passive"))
      (node (ref "R40") (pin "2") (pinfunction "2_2") (pintype "passive"))
      (node (ref "R41") (pin "1") (pinfunction "1_1") (pintype "passive"))
    )
    (net (code "65") (name "Net-(Q10-C)") (class "Default")
      (node (ref "Q10") (pin "3") (pinfunction "C_3") (pintype "passive"))
      (node (ref "R11") (pin "1") (pinfunction "1_1") (pintype "passive"))
    )
    (net (code "66") (name "Net-(Q11-B)") (class "Default")
      (node (ref "Q11") (pin "1") (pinfunction "B_1") (pintype "passive"))
      (node (ref "R44") (pin "2") (pinfunction "2_2") (pintype "passive"))
      (node (ref "R45") (pin "1") (pinfunction "1_1") (pintype "passive"))
    )
    (net (code "67") (name "Net-(Q11-C)") (class "Default")
      (node (ref "Q11") (pin "3") (pinfunction "C_3") (pintype "passive"))
      (node (ref "R7") (pin "1") (pinfunction "1_1") (pintype "passive"))
    )
    (net (code "68") (name "Net-(Q12-B)") (class "Default")
      (node (ref "Q12") (pin "1") (pinfunction "B_1") (pintype "passive"))
      (node (ref "R46") (pin "2") (pinfunction "2_2") (pintype "passive"))
      (node (ref "R47") (pin "1") (pinfunction "1_1") (pintype "passive"))
    )
    (net (code "69") (name "Net-(Q12-C)") (class "Default")
      (node (ref "Q12") (pin "3") (pinfunction "C_3") (pintype "passive"))
      (node (ref "R38") (pin "1") (pinfunction "1_1") (pintype "passive"))
    )
    (net (code "70") (name "Net-(Q13-B)") (class "Default")
      (node (ref "Q13") (pin "1") (pinfunction "B_1") (pintype "passive"))
      (node (ref "R48") (pin "2") (pinfunction "2_2") (pintype "passive"))
      (node (ref "R50") (pin "1") (pinfunction "1_1") (pintype "passive"))
    )
    (net (code "71") (name "Net-(Q13-C)") (class "Default")
      (node (ref "Q13") (pin "3") (pinfunction "C_3") (pintype "passive"))
      (node (ref "R31") (pin "1") (pinfunction "1_1") (pintype "passive"))
    )
    (net (code "72") (name "Net-(Q14-B)") (class "Default")
      (node (ref "Q14") (pin "1") (pinfunction "B_1") (pintype "passive"))
      (node (ref "R51") (pin "2") (pinfunction "2_2") (pintype "passive"))
      (node (ref "R52") (pin "1") (pinfunction "1_1") (pintype "passive"))
    )
    (net (code "73") (name "Net-(Q14-C)") (class "Default")
      (node (ref "Q14") (pin "3") (pinfunction "C_3") (pintype "passive"))
      (node (ref "R27") (pin "1") (pinfunction "1_1") (pintype "passive"))
    )
    (net (code "74") (name "Net-(Q15-B)") (class "Default")
      (node (ref "Q15") (pin "1") (pinfunction "B_1") (pintype "passive"))
      (node (ref "R53") (pin "2") (pinfunction "2_2") (pintype "passive"))
      (node (ref "R54") (pin "1") (pinfunction "1_1") (pintype "passive"))
    )
    (net (code "75") (name "Net-(Q15-C)") (class "Default")
      (node (ref "Q15") (pin "3") (pinfunction "C_3") (pintype "passive"))
      (node (ref "R23") (pin "1") (pinfunction "1_1") (pintype "passive"))
    )
    (net (code "76") (name "Net-(Q16-B)") (class "Default")
      (node (ref "Q16") (pin "1") (pinfunction "B_1") (pintype "passive"))
      (node (ref "R55") (pin "2") (pinfunction "2_2") (pintype "passive"))
      (node (ref "R56") (pin "1") (pinfunction "1_1") (pintype "passive"))
    )
    (net (code "77") (name "Net-(Q16-C)") (class "Default")
      (node (ref "Q16") (pin "3") (pinfunction "C_3") (pintype "passive"))
      (node (ref "R19") (pin "1") (pinfunction "1_1") (pintype "passive"))
    )
    (net (code "78") (name "Net-(R1-Pad2)") (class "Default")
      (node (ref "R1") (pin "2") (pinfunction "2_2") (pintype "passive"))
      (node (ref "RL1") (pin "+") (pinfunction "+_+") (pintype "passive"))
    )
    (net (code "79") (name "Net-(R2-Pad1)") (class "Default")
      (node (ref "R2") (pin "1") (pinfunction "1_1") (pintype "passive"))
      (node (ref "U1") (pin "3") (pinfunction "3_3") (pintype "bidirectional"))
    )
    (net (code "80") (name "Net-(R4-Pad2)") (class "Default")
      (node (ref "R4") (pin "2") (pinfunction "2_2") (pintype "passive"))
      (node (ref "RL4") (pin "+") (pinfunction "+_+") (pintype "passive"))
    )
    (net (code "81") (name "Net-(R5-Pad1)") (class "Default")
      (node (ref "R5") (pin "1") (pinfunction "1_1") (pintype "passive"))
      (node (ref "U4") (pin "3") (pinfunction "3_3") (pintype "bidirectional"))
    )
    (net (code "82") (name "Net-(R7-Pad2)") (class "Default")
      (node (ref "R7") (pin "2") (pinfunction "2_2") (pintype "passive"))
      (node (ref "U4") (pin "2") (pinfunction "2_2") (pintype "bidirectional"))
    )
    (net (code "83") (name "Net-(R8-Pad2)") (class "Default")
      (node (ref "R8") (pin "2") (pinfunction "2_2") (pintype "passive"))
      (node (ref "RL3") (pin "+") (pinfunction "+_+") (pintype "passive"))
    )
    (net (code "84") (name "Net-(R9-Pad1)") (class "Default")
      (node (ref "R9") (pin "1") (pinfunction "1_1") (pintype "passive"))
      (node (ref "U3") (pin "3") (pinfunction "3_3") (pintype "bidirectional"))
    )
    (net (code "85") (name "Net-(R11-Pad2)") (class "Default")
      (node (ref "R11") (pin "2") (pinfunction "2_2") (pintype "passive"))
      (node (ref "U3") (pin "2") (pinfunction "2_2") (pintype "bidirectional"))
    )
    (net (code "86") (name "Net-(R12-Pad2)") (class "Default")
      (node (ref "R12") (pin "2") (pinfunction "2_2") (pintype "passive"))
      (node (ref "RL2") (pin "+") (pinfunction "+_+") (pintype "passive"))
    )
    (net (code "87") (name "Net-(R13-Pad1)") (class "Default")
      (node (ref "R13") (pin "1") (pinfunction "1_1") (pintype "passive"))
      (node (ref "U2") (pin "3") (pinfunction "3_3") (pintype "bidirectional"))
    )
    (net (code "88") (name "Net-(R15-Pad2)") (class "Default")
      (node (ref "R15") (pin "2") (pinfunction "2_2") (pintype "passive"))
      (node (ref "U2") (pin "2") (pinfunction "2_2") (pintype "bidirectional"))
    )
    (net (code "89") (name "Net-(R16-Pad2)") (class "Default")
      (node (ref "R16") (pin "2") (pinfunction "2_2") (pintype "passive"))
      (node (ref "RL5") (pin "+") (pinfunction "+_+") (pintype "passive"))
    )
    (net (code "90") (name "Net-(R17-Pad1)") (class "Default")
      (node (ref "R17") (pin "1") (pinfunction "1_1") (pintype "passive"))
      (node (ref "U5") (pin "3") (pinfunction "3_3") (pintype "bidirectional"))
    )
    (net (code "91") (name "Net-(R19-Pad2)") (class "Default")
      (node (ref "R19") (pin "2") (pinfunction "2_2") (pintype "passive"))
      (node (ref "U5") (pin "2") (pinfunction "2_2") (pintype "bidirectional"))
    )
    (net (code "92") (name "Net-(R20-Pad2)") (class "Default")
      (node (ref "R20") (pin "2") (pinfunction "2_2") (pintype "passive"))
      (node (ref "RL6") (pin "+") (pinfunction "+_+") (pintype "passive"))
    )
    (net (code "93") (name "Net-(R21-Pad1)") (class "Default")
      (node (ref "R21") (pin "1") (pinfunction "1_1") (pintype "passive"))
      (node (ref "U6") (pin "3") (pinfunction "3_3") (pintype "bidirectional"))
    )
    (net (code "94") (name "Net-(R23-Pad2)") (class "Default")
      (node (ref "R23") (pin "2") (pinfunction "2_2") (pintype "passive"))
      (node (ref "U6") (pin "2") (pinfunction "2_2") (pintype "bidirectional"))
    )
    (net (code "95") (name "Net-(R24-Pad2)") (class "Default")
      (node (ref "R24") (pin "2") (pinfunction "2_2") (pintype "passive"))
      (node (ref "RL7") (pin "+") (pinfunction "+_+") (pintype "passive"))
    )
    (net (code "96") (name "Net-(R25-Pad1)") (class "Default")
      (node (ref "R25") (pin "1") (pinfunction "1_1") (pintype "passive"))
      (node (ref "U8") (pin "3") (pinfunction "3_3") (pintype "bidirectional"))
    )
    (net (code "97") (name "Net-(R27-Pad2)") (class "Default")
      (node (ref "R27") (pin "2") (pinfunction "2_2") (pintype "passive"))
      (node (ref "U8") (pin "2") (pinfunction "2_2") (pintype "bidirectional"))
    )
    (net (code "98") (name "Net-(R28-Pad2)") (class "Default")
      (node (ref "R28") (pin "2") (pinfunction "2_2") (pintype "passive"))
      (node (ref "RL8") (pin "+") (pinfunction "+_+") (pintype "passive"))
    )
    (net (code "99") (name "Net-(R29-Pad1)") (class "Default")
      (node (ref "R29") (pin "1") (pinfunction "1_1") (pintype "passive"))
      (node (ref "U7") (pin "3") (pinfunction "3_3") (pintype "bidirectional"))
    )
    (net (code "100") (name "Net-(R31-Pad2)") (class "Default")
      (node (ref "R31") (pin "2") (pinfunction "2_2") (pintype "passive"))
      (node (ref "U7") (pin "2") (pinfunction "2_2") (pintype "bidirectional"))
    )
    (net (code "101") (name "Net-(R38-Pad2)") (class "Default")
      (node (ref "R38") (pin "2") (pinfunction "2_2") (pintype "passive"))
      (node (ref "U1") (pin "2") (pinfunction "2_2") (pintype "bidirectional"))
    )
    (net (code "102") (name "Net-(U9-BS)") (class "Default")
      (node (ref "C19") (pin "1") (pinfunction "1_1") (pintype "passive"))
      (node (ref "U9") (pin "1") (pinfunction "BS_1") (pintype "bidirectional"))
    )
    (net (code "103") (name "Net-(U9-EN)") (class "Default")
      (node (ref "PWR") (pin "COM1") (pinfunction "COM1_COM1") (pintype "bidirectional"))
      (node (ref "PWR") (pin "COM2") (pinfunction "COM2_COM2") (pintype "bidirectional"))
      (node (ref "R37") (pin "2") (pinfunction "2_2") (pintype "passive"))
      (node (ref "U9") (pin "4") (pinfunction "EN_4") (pintype "bidirectional"))
    )
    (net (code "104") (name "Net-(U9-FB)") (class "Default")
      (node (ref "C20") (pin "1") (pinfunction "1_1") (pintype "passive"))
      (node (ref "R35") (pin "2") (pinfunction "2_2") (pintype "passive"))
      (node (ref "R36") (pin "1") (pinfunction "1_1") (pintype "passive"))
      (node (ref "U9") (pin "3") (pinfunction "FB_3") (pintype "bidirectional"))
    )
    (net (code "105") (name "Net-(U9-LX)") (class "Default")
      (node (ref "C19") (pin "2") (pinfunction "2_2") (pintype "passive"))
      (node (ref "D9") (pin "-") (pinfunction "-_-") (pintype "passive"))
      (node (ref "L1") (pin "1") (pinfunction "1_1") (pintype "passive"))
      (node (ref "U9") (pin "6") (pinfunction "LX_6") (pintype "bidirectional"))
    )
    (net (code "106") (name "VCC") (class "Default")
      (node (ref "D1") (pin "C") (pinfunction "C_C") (pintype "passive"))
      (node (ref "D2") (pin "C") (pinfunction "C_C") (pintype "passive"))
      (node (ref "D3") (pin "C") (pinfunction "C_C") (pintype "passive"))
      (node (ref "D4") (pin "C") (pinfunction "C_C") (pintype "passive"))
      (node (ref "D5") (pin "C") (pinfunction "C_C") (pintype "passive"))
      (node (ref "D6") (pin "C") (pinfunction "C_C") (pintype "passive"))
      (node (ref "D7") (pin "C") (pinfunction "C_C") (pintype "passive"))
      (node (ref "D8") (pin "C") (pinfunction "C_C") (pintype "passive"))
      (node (ref "K1") (pin "1") (pinfunction "1_1") (pintype "bidirectional"))
      (node (ref "K2") (pin "1") (pinfunction "1_1") (pintype "bidirectional"))
      (node (ref "K3") (pin "1") (pinfunction "1_1") (pintype "bidirectional"))
      (node (ref "K4") (pin "1") (pinfunction "1_1") (pintype "bidirectional"))
      (node (ref "K5") (pin "1") (pinfunction "1_1") (pintype "bidirectional"))
      (node (ref "K6") (pin "1") (pinfunction "1_1") (pintype "bidirectional"))
      (node (ref "K7") (pin "1") (pinfunction "1_1") (pintype "bidirectional"))
      (node (ref "K8") (pin "1") (pinfunction "1_1") (pintype "bidirectional"))
      (node (ref "R1") (pin "1") (pinfunction "1_1") (pintype "passive"))
      (node (ref "R12") (pin "1") (pinfunction "1_1") (pintype "passive"))
      (node (ref "R16") (pin "1") (pinfunction "1_1") (pintype "passive"))
      (node (ref "R20") (pin "1") (pinfunction "1_1") (pintype "passive"))
      (node (ref "R24") (pin "1") (pinfunction "1_1") (pintype "passive"))
      (node (ref "R28") (pin "1") (pinfunction "1_1") (pintype "passive"))
      (node (ref "R4") (pin "1") (pinfunction "1_1") (pintype "passive"))
      (node (ref "R49") (pin "2") (pinfunction "2_2") (pintype "passive"))
      (node (ref "R57") (pin "2") (pinfunction "2_2") (pintype "passive"))
      (node (ref "R8") (pin "1") (pinfunction "1_1") (pintype "passive"))
    )
    (net (code "107") (name "unconnected-(J1-Pad23)") (class "Default")
      (node (ref "J1") (pin "23") (pinfunction "23_23") (pintype "bidirectional"))
    )
    (net (code "108") (name "unconnected-(PWR-PadCH1A)") (class "Default")
      (node (ref "PWR") (pin "CH1A") (pinfunction "CH1A_CH1A") (pintype "bidirectional"))
    )
    (net (code "109") (name "unconnected-(PWR-PadCH2A)") (class "Default")
      (node (ref "PWR") (pin "CH2A") (pinfunction "CH2A_CH2A") (pintype "bidirectional"))
    )
  )
)
